# PowerManagement_Base_v2.net
KiCad netlist of a schematic drawn in Altium Designer
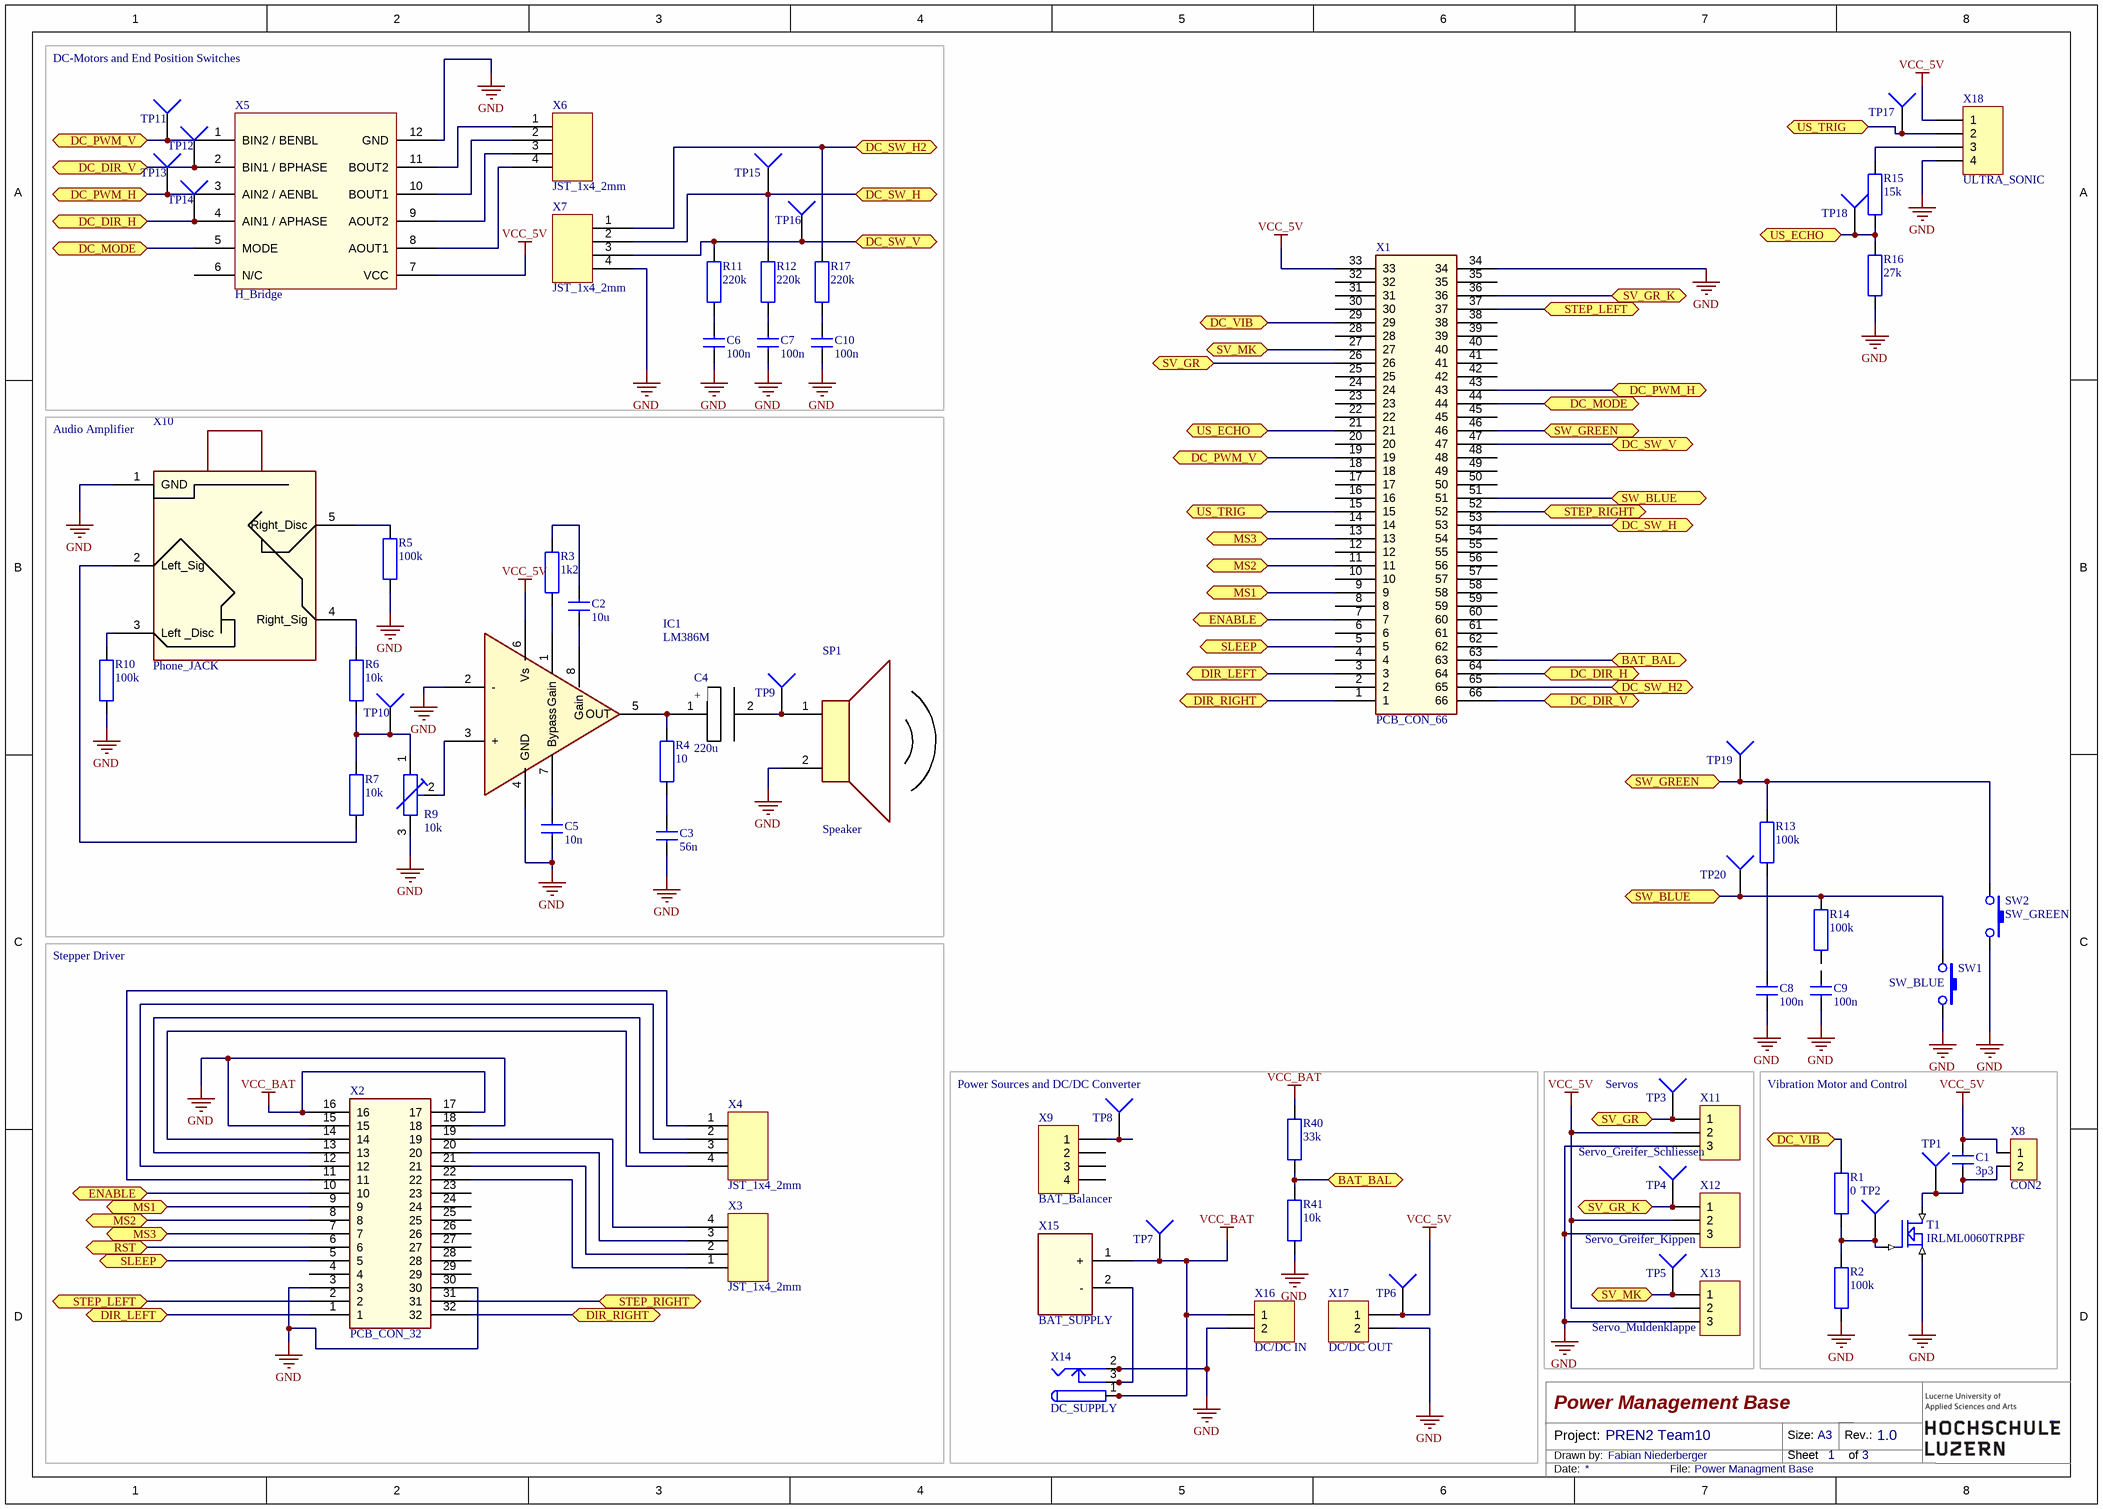
[diagram p0: PowerManagement_Base_v2.SchDoc]

(export (version "E")
  (design (tool "Eeschema 10.0.6"))
  (components
    (comp (ref "C1")
      (value "3p3")
      (footprint "0805")
      (description "Normaler Kondensator")
      (libsource (lib "DEVICE_HSLU") (part "C?"))
    )
    (comp (ref "C2")
      (value "10u")
      (footprint "0805")
      (description "Normaler Kondensator")
      (libsource (lib "DEVICE_HSLU") (part "C?"))
    )
    (comp (ref "C3")
      (value "56n")
      (footprint "0805")
      (description "Normaler Kondensator")
      (libsource (lib "DEVICE_HSLU") (part "C?"))
    )
    (comp (ref "C4")
      (value "220u")
      (footprint "Elko")
      (description "Electrolyt Capacitor")
      (libsource (lib "PREN2Lib") (part "Elko"))
    )
    (comp (ref "C5")
      (value "10n")
      (footprint "0805")
      (description "Normaler Kondensator")
      (libsource (lib "DEVICE_HSLU") (part "C?"))
    )
    (comp (ref "C6")
      (value "100n")
      (footprint "0805")
      (description "Normaler Kondensator")
      (libsource (lib "DEVICE_HSLU") (part "C?"))
    )
    (comp (ref "C7")
      (value "100n")
      (footprint "0805")
      (description "Normaler Kondensator")
      (libsource (lib "DEVICE_HSLU") (part "C?"))
    )
    (comp (ref "C8")
      (value "100n")
      (footprint "0805")
      (description "Normaler Kondensator")
      (libsource (lib "DEVICE_HSLU") (part "C?"))
    )
    (comp (ref "C9")
      (value "100n")
      (footprint "0805")
      (description "Normaler Kondensator")
      (libsource (lib "DEVICE_HSLU") (part "C?"))
    )
    (comp (ref "C10")
      (value "100n")
      (footprint "0805")
      (description "Normaler Kondensator")
      (libsource (lib "DEVICE_HSLU") (part "C?"))
    )
    (comp (ref "IC1")
      (value "LM386M")
      (footprint "SO-8")
      (description "Audio AMP in SO-8 Package")
      (libsource (lib "PREN2Lib") (part "Audio Amp"))
    )
    (comp (ref "R1")
      (value "0")
      (footprint "0805")
      (description "Normaler Widerstand")
      (libsource (lib "DEVICE_HSLU") (part "R?"))
    )
    (comp (ref "R2")
      (value "100k")
      (footprint "0805")
      (description "Normaler Widerstand")
      (libsource (lib "DEVICE_HSLU") (part "R?"))
    )
    (comp (ref "R3")
      (value "1k2")
      (footprint "0805")
      (description "Normaler Widerstand")
      (libsource (lib "DEVICE_HSLU") (part "R?"))
    )
    (comp (ref "R4")
      (value "10")
      (footprint "0805")
      (description "Normaler Widerstand")
      (libsource (lib "DEVICE_HSLU") (part "R?"))
    )
    (comp (ref "R5")
      (value "100k")
      (footprint "0805")
      (description "Normaler Widerstand")
      (libsource (lib "DEVICE_HSLU") (part "R?"))
    )
    (comp (ref "R6")
      (value "10k")
      (footprint "0805")
      (description "Normaler Widerstand")
      (libsource (lib "DEVICE_HSLU") (part "R?"))
    )
    (comp (ref "R7")
      (value "10k")
      (footprint "0805")
      (description "Normaler Widerstand")
      (libsource (lib "DEVICE_HSLU") (part "R?"))
    )
    (comp (ref "R9") (value "10k") (footprint "POT2") (libsource (lib "DEVICE_HSLU") (part "R_POT1")))
    (comp (ref "R10")
      (value "100k")
      (footprint "0805")
      (description "Normaler Widerstand")
      (libsource (lib "DEVICE_HSLU") (part "R?"))
    )
    (comp (ref "R11")
      (value "220k")
      (footprint "0805")
      (description "Normaler Widerstand")
      (libsource (lib "DEVICE_HSLU") (part "R?"))
    )
    (comp (ref "R12")
      (value "220k")
      (footprint "0805")
      (description "Normaler Widerstand")
      (libsource (lib "DEVICE_HSLU") (part "R?"))
    )
    (comp (ref "R13")
      (value "100k")
      (footprint "0805")
      (description "Normaler Widerstand")
      (libsource (lib "DEVICE_HSLU") (part "R?"))
    )
    (comp (ref "R14")
      (value "100k")
      (footprint "0805")
      (description "Normaler Widerstand")
      (libsource (lib "DEVICE_HSLU") (part "R?"))
    )
    (comp (ref "R15")
      (value "15k")
      (footprint "0805")
      (description "Normaler Widerstand")
      (libsource (lib "DEVICE_HSLU") (part "R?"))
    )
    (comp (ref "R16")
      (value "27k")
      (footprint "0805")
      (description "Normaler Widerstand")
      (libsource (lib "DEVICE_HSLU") (part "R?"))
    )
    (comp (ref "R17")
      (value "220k")
      (footprint "0805")
      (description "Normaler Widerstand")
      (libsource (lib "DEVICE_HSLU") (part "R?"))
    )
    (comp (ref "R40")
      (value "33k")
      (footprint "0805")
      (description "Normaler Widerstand")
      (libsource (lib "DEVICE_HSLU") (part "R?"))
    )
    (comp (ref "R41")
      (value "10k")
      (footprint "0805")
      (description "Normaler Widerstand")
      (libsource (lib "DEVICE_HSLU") (part "R?"))
    )
    (comp (ref "SP1")
      (value "Speaker")
      (footprint "Speaker")
      (description "8 Ohm Speaker")
      (libsource (lib "PREN2Lib") (part "Speaker"))
    )
    (comp (ref "SW1") (value "SW_BLUE") (footprint "TASTER") (libsource (lib "DEVICE_HSLU") (part "SW-PB")))
    (comp (ref "SW2") (value "SW_GREEN") (footprint "TASTER") (libsource (lib "DEVICE_HSLU") (part "SW-PB")))
    (comp (ref "T1")
      (value "IRLML0060TRPBF")
      (footprint "SOT-23")
      (libsource (lib "DEVICE_HSLU") (part "MOSFET N"))
    )
    (comp (ref "TP1")
      (value "~")
      (footprint "PIN1")
      (fields (field (name "PUBLISHER") "Altium Limited"))
      (libsource (lib "Miscellaneous Connectors") (part "Socket"))
    )
    (comp (ref "TP2")
      (value "~")
      (footprint "PIN1")
      (fields (field (name "PUBLISHER") "Altium Limited"))
      (libsource (lib "Miscellaneous Connectors") (part "Socket"))
    )
    (comp (ref "TP3")
      (value "~")
      (footprint "PIN1")
      (fields (field (name "PUBLISHER") "Altium Limited"))
      (libsource (lib "Miscellaneous Connectors") (part "Socket"))
    )
    (comp (ref "TP4")
      (value "~")
      (footprint "PIN1")
      (fields (field (name "PUBLISHER") "Altium Limited"))
      (libsource (lib "Miscellaneous Connectors") (part "Socket"))
    )
    (comp (ref "TP5")
      (value "~")
      (footprint "PIN1")
      (fields (field (name "PUBLISHER") "Altium Limited"))
      (libsource (lib "Miscellaneous Connectors") (part "Socket"))
    )
    (comp (ref "TP6")
      (value "~")
      (footprint "PIN1")
      (fields (field (name "PUBLISHER") "Altium Limited"))
      (libsource (lib "Miscellaneous Connectors") (part "Socket"))
    )
    (comp (ref "TP7")
      (value "~")
      (footprint "PIN1")
      (fields (field (name "PUBLISHER") "Altium Limited"))
      (libsource (lib "Miscellaneous Connectors") (part "Socket"))
    )
    (comp (ref "TP8")
      (value "~")
      (footprint "PIN1")
      (fields (field (name "PUBLISHER") "Altium Limited"))
      (libsource (lib "Miscellaneous Connectors") (part "Socket"))
    )
    (comp (ref "TP9")
      (value "~")
      (footprint "PIN1")
      (fields (field (name "PUBLISHER") "Altium Limited"))
      (libsource (lib "Miscellaneous Connectors") (part "Socket"))
    )
    (comp (ref "TP10")
      (value "~")
      (footprint "PIN1")
      (fields (field (name "PUBLISHER") "Altium Limited"))
      (libsource (lib "Miscellaneous Connectors") (part "Socket"))
    )
    (comp (ref "TP11")
      (value "~")
      (footprint "PIN1")
      (fields (field (name "PUBLISHER") "Altium Limited"))
      (libsource (lib "Miscellaneous Connectors") (part "Socket"))
    )
    (comp (ref "TP12")
      (value "~")
      (footprint "PIN1")
      (fields (field (name "PUBLISHER") "Altium Limited"))
      (libsource (lib "Miscellaneous Connectors") (part "Socket"))
    )
    (comp (ref "TP13")
      (value "~")
      (footprint "PIN1")
      (fields (field (name "PUBLISHER") "Altium Limited"))
      (libsource (lib "Miscellaneous Connectors") (part "Socket"))
    )
    (comp (ref "TP14")
      (value "~")
      (footprint "PIN1")
      (fields (field (name "PUBLISHER") "Altium Limited"))
      (libsource (lib "Miscellaneous Connectors") (part "Socket"))
    )
    (comp (ref "TP15")
      (value "~")
      (footprint "PIN1")
      (fields (field (name "PUBLISHER") "Altium Limited"))
      (libsource (lib "Miscellaneous Connectors") (part "Socket"))
    )
    (comp (ref "TP16")
      (value "~")
      (footprint "PIN1")
      (fields (field (name "PUBLISHER") "Altium Limited"))
      (libsource (lib "Miscellaneous Connectors") (part "Socket"))
    )
    (comp (ref "TP17")
      (value "~")
      (footprint "PIN1")
      (fields (field (name "PUBLISHER") "Altium Limited"))
      (libsource (lib "Miscellaneous Connectors") (part "Socket"))
    )
    (comp (ref "TP18")
      (value "~")
      (footprint "PIN1")
      (fields (field (name "PUBLISHER") "Altium Limited"))
      (libsource (lib "Miscellaneous Connectors") (part "Socket"))
    )
    (comp (ref "TP19")
      (value "~")
      (footprint "PIN1")
      (fields (field (name "PUBLISHER") "Altium Limited"))
      (libsource (lib "Miscellaneous Connectors") (part "Socket"))
    )
    (comp (ref "TP20")
      (value "~")
      (footprint "PIN1")
      (fields (field (name "PUBLISHER") "Altium Limited"))
      (libsource (lib "Miscellaneous Connectors") (part "Socket"))
    )
    (comp (ref "X1")
      (value "PCB_CON_66")
      (footprint "PCB_CON_66_JACK")
      (description "Connects a PCB with another. This scheme is either jack or plug, depends on footprint")
      (libsource (lib "PREN2Lib") (part "PCB_CON_66"))
    )
    (comp (ref "X2")
      (value "PCB_CON_32")
      (footprint "PCB_CON_32_JACK")
      (description "Connects a PCB with another. This scheme is either jack or plug, depends on footprint")
      (libsource (lib "PREN2Lib") (part "PCB_CON_32"))
    )
    (comp (ref "X3")
      (value "JST_1x4_2mm")
      (footprint "JST_1x4_2mm_horizontal")
      (description "JST connector single row 4 pin, 2mm grid")
      (libsource (lib "") (part "JST_1x4_2mm_2"))
    )
    (comp (ref "X4")
      (value "JST_1x4_2mm")
      (footprint "JST_1x4_2mm_horizontal")
      (description "JST connector single row 4 pin, 2mm grid")
      (libsource (lib "") (part "JST_1x4_2mm_1"))
    )
    (comp (ref "X5")
      (value "H_Bridge")
      (footprint "H_Bridge")
      (description "H-Bridge Shield")
      (libsource (lib "PREN2Lib") (part "H_Bridge"))
    )
    (comp (ref "X6")
      (value "JST_1x4_2mm")
      (footprint "JST_1x4_2mm_horizontal")
      (description "JST connector single row 4 pin, 2mm grid")
      (libsource (lib "") (part "JST_1x4_2mm_1"))
    )
    (comp (ref "X7")
      (value "JST_1x4_2mm")
      (footprint "JST_1x4_2mm_horizontal")
      (description "JST connector single row 4 pin, 2mm grid")
      (libsource (lib "PREN2Lib") (part "JST_1x4_2mm"))
    )
    (comp (ref "X8") (value "CON2") (footprint "HDR1X2") (libsource (lib "DEVICE_HSLU") (part "CON2")))
    (comp (ref "X9")
      (value "BAT_Balancer")
      (footprint "HDR1X4")
      (description "Header, 4-Pin")
      (fields (field (name "PUBLISHER") "Altium Limited"))
      (libsource (lib "") (part "Header 4_1"))
    )
    (comp (ref "X10")
      (value "Phone_JACK")
      (footprint "Audio_CON 3.5mm")
      (description "3.5 mm Phone Jack Stereo with Disconnect information")
      (libsource (lib "PREN2Lib") (part "Phone_JACK"))
    )
    (comp (ref "X11")
      (value "Servo_Greifer_Schliessen")
      (footprint "HDR1X3")
      (description "Header, 3-Pin")
      (fields (field (name "PUBLISHER") "Altium Limited"))
      (libsource (lib "Miscellaneous Connectors") (part "Header 3"))
    )
    (comp (ref "X12")
      (value "Servo_Greifer_Kippen")
      (footprint "HDR1X3")
      (description "Header, 3-Pin")
      (fields (field (name "PUBLISHER") "Altium Limited"))
      (libsource (lib "Miscellaneous Connectors") (part "Header 3"))
    )
    (comp (ref "X13")
      (value "Servo_Muldenklappe")
      (footprint "HDR1X3")
      (description "Header, 3-Pin")
      (fields (field (name "PUBLISHER") "Altium Limited"))
      (libsource (lib "Miscellaneous Connectors") (part "Header 3"))
    )
    (comp (ref "X14")
      (value "DC_SUPPLY")
      (footprint "KLD-0202")
      (description "Low Voltage Power Supply Connector")
      (fields (field (name "PUBLISHER") "Altium Limited"))
      (libsource (lib "Miscellaneous Connectors") (part "PWR2.5"))
    )
    (comp (ref "X15")
      (value "BAT_SUPPLY")
      (footprint "XT60_CON")
      (description "XT60 LiPo Accumulator Connector")
      (libsource (lib "PREN2Lib") (part "XT60_CON"))
    )
    (comp (ref "X16")
      (value "DC/DC IN")
      (footprint "HDR1X2H")
      (description "Header, 2-Pin, Right Angle")
      (fields (field (name "PUBLISHER") "Altium Limited"))
      (libsource (lib "Miscellaneous Connectors") (part "Header 2H"))
    )
    (comp (ref "X17")
      (value "DC/DC OUT")
      (footprint "HDR1X2H")
      (description "Header, 2-Pin, Right Angle")
      (fields (field (name "PUBLISHER") "Altium Limited"))
      (libsource (lib "") (part "Header 2H_1"))
    )
    (comp (ref "X18")
      (value "ULTRA_SONIC")
      (footprint "HDR1X4")
      (description "Header, 4-Pin")
      (fields (field (name "PUBLISHER") "Altium Limited"))
      (libsource (lib "Miscellaneous Connectors") (part "Header 4"))
    )
  )
  (nets
    (net (code "1") (name "/BAT_BAL") (class "Default")
      (node (ref "R40") (pin "1") (pintype "passive"))
      (node (ref "R41") (pin "2") (pintype "passive"))
      (node (ref "X1") (pin "63") (pinfunction "63_63") (pintype "passive"))
    )
    (net (code "2") (name "/DC_DIR_H") (class "Default")
      (node (ref "TP14") (pin "1") (pinfunction "1_1") (pintype "passive"))
      (node (ref "X1") (pin "64") (pinfunction "64_64") (pintype "passive"))
      (node (ref "X5") (pin "4") (pinfunction "AIN1_/_APHASE_4") (pintype "passive"))
    )
    (net (code "3") (name "/DC_DIR_V") (class "Default")
      (node (ref "TP12") (pin "1") (pinfunction "1_1") (pintype "passive"))
      (node (ref "X1") (pin "66") (pinfunction "66_66") (pintype "passive"))
      (node (ref "X5") (pin "2") (pinfunction "BIN1_/_BPHASE_2") (pintype "passive"))
    )
    (net (code "4") (name "/DC_MODE") (class "Default")
      (node (ref "X1") (pin "44") (pinfunction "44_44") (pintype "passive"))
      (node (ref "X5") (pin "5") (pinfunction "MODE_5") (pintype "passive"))
    )
    (net (code "5") (name "/DC_PWM_H") (class "Default")
      (node (ref "TP13") (pin "1") (pinfunction "1_1") (pintype "passive"))
      (node (ref "X1") (pin "43") (pinfunction "43_43") (pintype "passive"))
      (node (ref "X5") (pin "3") (pinfunction "AIN2_/_AENBL_3") (pintype "passive"))
    )
    (net (code "6") (name "/DC_PWM_V") (class "Default")
      (node (ref "TP11") (pin "1") (pinfunction "1_1") (pintype "passive"))
      (node (ref "X1") (pin "19") (pinfunction "19_19") (pintype "passive"))
      (node (ref "X5") (pin "1") (pinfunction "BIN2_/_BENBL_1") (pintype "passive"))
    )
    (net (code "7") (name "/DC_SW_H") (class "Default")
      (node (ref "R12") (pin "2") (pintype "passive"))
      (node (ref "TP15") (pin "1") (pinfunction "1_1") (pintype "passive"))
      (node (ref "X1") (pin "53") (pinfunction "53_53") (pintype "passive"))
      (node (ref "X7") (pin "2") (pintype "passive"))
    )
    (net (code "8") (name "/DC_SW_H2") (class "Default")
      (node (ref "R17") (pin "2") (pintype "passive"))
      (node (ref "X1") (pin "65") (pinfunction "65_65") (pintype "passive"))
      (node (ref "X7") (pin "1") (pintype "passive"))
    )
    (net (code "9") (name "/DC_SW_V") (class "Default")
      (node (ref "R11") (pin "2") (pintype "passive"))
      (node (ref "TP16") (pin "1") (pinfunction "1_1") (pintype "passive"))
      (node (ref "X1") (pin "47") (pinfunction "47_47") (pintype "passive"))
      (node (ref "X7") (pin "3") (pintype "passive"))
    )
    (net (code "10") (name "/DC_VIB") (class "Default")
      (node (ref "R1") (pin "2") (pintype "passive"))
      (node (ref "X1") (pin "29") (pinfunction "29_29") (pintype "passive"))
    )
    (net (code "11") (name "/DIR_LEFT") (class "Default")
      (node (ref "X1") (pin "3") (pinfunction "3_3") (pintype "passive"))
      (node (ref "X2") (pin "1") (pinfunction "1_1") (pintype "passive"))
    )
    (net (code "12") (name "/DIR_RIGHT") (class "Default")
      (node (ref "X1") (pin "1") (pinfunction "1_1") (pintype "passive"))
      (node (ref "X2") (pin "32") (pinfunction "32_32") (pintype "passive"))
    )
    (net (code "13") (name "/ENABLE") (class "Default")
      (node (ref "X1") (pin "7") (pinfunction "7_7") (pintype "passive"))
      (node (ref "X2") (pin "10") (pinfunction "10_10") (pintype "passive"))
    )
    (net (code "14") (name "/MS1") (class "Default")
      (node (ref "X1") (pin "9") (pinfunction "9_9") (pintype "passive"))
      (node (ref "X2") (pin "9") (pinfunction "9_9") (pintype "passive"))
    )
    (net (code "15") (name "/MS2") (class "Default")
      (node (ref "X1") (pin "11") (pinfunction "11_11") (pintype "passive"))
      (node (ref "X2") (pin "8") (pinfunction "8_8") (pintype "passive"))
    )
    (net (code "16") (name "/MS3") (class "Default")
      (node (ref "X1") (pin "13") (pinfunction "13_13") (pintype "passive"))
      (node (ref "X2") (pin "7") (pinfunction "7_7") (pintype "passive"))
    )
    (net (code "17") (name "/RST") (class "Default")
      (node (ref "X2") (pin "6") (pinfunction "6_6") (pintype "passive"))
    )
    (net (code "18") (name "/SLEEP") (class "Default")
      (node (ref "X1") (pin "5") (pinfunction "5_5") (pintype "passive"))
      (node (ref "X2") (pin "5") (pinfunction "5_5") (pintype "passive"))
    )
    (net (code "19") (name "/STEP_LEFT") (class "Default")
      (node (ref "X1") (pin "37") (pinfunction "37_37") (pintype "passive"))
      (node (ref "X2") (pin "2") (pinfunction "2_2") (pintype "passive"))
    )
    (net (code "20") (name "/STEP_RIGHT") (class "Default")
      (node (ref "X1") (pin "52") (pinfunction "52_52") (pintype "passive"))
      (node (ref "X2") (pin "31") (pinfunction "31_31") (pintype "passive"))
    )
    (net (code "21") (name "/SV_GR") (class "Default")
      (node (ref "TP3") (pin "1") (pinfunction "1_1") (pintype "passive"))
      (node (ref "X1") (pin "26") (pinfunction "26_26") (pintype "passive"))
      (node (ref "X11") (pin "1") (pinfunction "1_1") (pintype "passive"))
    )
    (net (code "22") (name "/SV_GR_K") (class "Default")
      (node (ref "TP4") (pin "1") (pinfunction "1_1") (pintype "passive"))
      (node (ref "X1") (pin "36") (pinfunction "36_36") (pintype "passive"))
      (node (ref "X12") (pin "1") (pinfunction "1_1") (pintype "passive"))
    )
    (net (code "23") (name "/SV_MK") (class "Default")
      (node (ref "TP5") (pin "1") (pinfunction "1_1") (pintype "passive"))
      (node (ref "X1") (pin "27") (pinfunction "27_27") (pintype "passive"))
      (node (ref "X13") (pin "1") (pinfunction "1_1") (pintype "passive"))
    )
    (net (code "24") (name "/SW_BLUE") (class "Default")
      (node (ref "R14") (pin "2") (pintype "passive"))
      (node (ref "SW1") (pin "1") (pintype "passive"))
      (node (ref "TP20") (pin "1") (pinfunction "1_1") (pintype "passive"))
      (node (ref "X1") (pin "51") (pinfunction "51_51") (pintype "passive"))
    )
    (net (code "25") (name "/SW_GREEN") (class "Default")
      (node (ref "R13") (pin "2") (pintype "passive"))
      (node (ref "SW2") (pin "1") (pintype "passive"))
      (node (ref "TP19") (pin "1") (pinfunction "1_1") (pintype "passive"))
      (node (ref "X1") (pin "46") (pinfunction "46_46") (pintype "passive"))
    )
    (net (code "26") (name "/US_ECHO") (class "Default")
      (node (ref "R15") (pin "1") (pintype "passive"))
      (node (ref "R16") (pin "2") (pintype "passive"))
      (node (ref "TP18") (pin "1") (pinfunction "1_1") (pintype "passive"))
      (node (ref "X1") (pin "21") (pinfunction "21_21") (pintype "passive"))
    )
    (net (code "27") (name "/US_TRIG") (class "Default")
      (node (ref "TP17") (pin "1") (pinfunction "1_1") (pintype "passive"))
      (node (ref "X1") (pin "15") (pinfunction "15_15") (pintype "passive"))
      (node (ref "X18") (pin "2") (pinfunction "2_2") (pintype "passive"))
    )
    (net (code "28") (name "GND") (class "Default")
      (node (ref "C10") (pin "2") (pinfunction "2_2") (pintype "passive"))
      (node (ref "C3") (pin "2") (pinfunction "2_2") (pintype "passive"))
      (node (ref "C5") (pin "2") (pinfunction "2_2") (pintype "passive"))
      (node (ref "C6") (pin "2") (pinfunction "2_2") (pintype "passive"))
      (node (ref "C7") (pin "2") (pinfunction "2_2") (pintype "passive"))
      (node (ref "C8") (pin "2") (pinfunction "2_2") (pintype "passive"))
      (node (ref "C9") (pin "2") (pinfunction "2_2") (pintype "passive"))
      (node (ref "IC1") (pin "2") (pinfunction "-_2") (pintype "passive"))
      (node (ref "IC1") (pin "4") (pinfunction "GND_4") (pintype "passive"))
      (node (ref "R10") (pin "1") (pintype "passive"))
      (node (ref "R16") (pin "1") (pintype "passive"))
      (node (ref "R2") (pin "1") (pintype "passive"))
      (node (ref "R41") (pin "1") (pintype "passive"))
      (node (ref "R5") (pin "1") (pintype "passive"))
      (node (ref "R9") (pin "3") (pintype "passive"))
      (node (ref "SP1") (pin "2") (pinfunction "2_2") (pintype "passive"))
      (node (ref "SW1") (pin "2") (pintype "passive"))
      (node (ref "SW2") (pin "2") (pintype "passive"))
      (node (ref "T1") (pin "SOURCE") (pinfunction "SOURCE_SOURCE") (pintype "input"))
      (node (ref "X1") (pin "34") (pinfunction "34_34") (pintype "passive"))
      (node (ref "X10") (pin "1") (pinfunction "GND_1") (pintype "passive"))
      (node (ref "X11") (pin "3") (pinfunction "3_3") (pintype "passive"))
      (node (ref "X12") (pin "3") (pinfunction "3_3") (pintype "passive"))
      (node (ref "X13") (pin "3") (pinfunction "3_3") (pintype "passive"))
      (node (ref "X14") (pin "2") (pinfunction "2_2") (pintype "power_in"))
      (node (ref "X14") (pin "2A") (pinfunction "2A_2A") (pintype "power_in"))
      (node (ref "X14") (pin "2B") (pinfunction "2B_2B") (pintype "power_in"))
      (node (ref "X16") (pin "2") (pinfunction "2_2") (pintype "passive"))
      (node (ref "X17") (pin "2") (pinfunction "2_2") (pintype "passive"))
      (node (ref "X18") (pin "4") (pinfunction "4_4") (pintype "passive"))
      (node (ref "X2") (pin "15") (pinfunction "15_15") (pintype "passive"))
      (node (ref "X2") (pin "18") (pinfunction "18_18") (pintype "passive"))
      (node (ref "X2") (pin "3") (pinfunction "3_3") (pintype "passive"))
      (node (ref "X2") (pin "30") (pinfunction "30_30") (pintype "passive"))
      (node (ref "X5") (pin "12") (pinfunction "GND_12") (pintype "power_in"))
      (node (ref "X7") (pin "4") (pintype "passive"))
    )
    (net (code "29") (name "Net-(C1-Pad1)") (class "Default")
      (node (ref "C1") (pin "1") (pinfunction "1_1") (pintype "passive"))
      (node (ref "T1") (pin "DRAIN") (pinfunction "DRAIN_DRAIN") (pintype "input"))
      (node (ref "TP1") (pin "1") (pinfunction "1_1") (pintype "passive"))
      (node (ref "X8") (pin "2") (pinfunction "2_2") (pintype "passive"))
    )
    (net (code "30") (name "Net-(C2-Pad1)") (class "Default")
      (node (ref "C2") (pin "1") (pinfunction "1_1") (pintype "passive"))
      (node (ref "R3") (pin "2") (pintype "passive"))
    )
    (net (code "31") (name "Net-(C2-Pad2)") (class "Default")
      (node (ref "C2") (pin "2") (pinfunction "2_2") (pintype "passive"))
      (node (ref "IC1") (pin "8") (pinfunction "Gain_8") (pintype "passive"))
    )
    (net (code "32") (name "Net-(C3-Pad1)") (class "Default")
      (node (ref "C3") (pin "1") (pinfunction "1_1") (pintype "passive"))
      (node (ref "R4") (pin "1") (pintype "passive"))
    )
    (net (code "33") (name "Net-(C4-Pad2)") (class "Default")
      (node (ref "C4") (pin "2") (pintype "passive"))
      (node (ref "SP1") (pin "1") (pinfunction "1_1") (pintype "passive"))
      (node (ref "TP9") (pin "1") (pinfunction "1_1") (pintype "passive"))
    )
    (net (code "34") (name "Net-(C6-Pad1)") (class "Default")
      (node (ref "C6") (pin "1") (pinfunction "1_1") (pintype "passive"))
      (node (ref "R11") (pin "1") (pintype "passive"))
    )
    (net (code "35") (name "Net-(C7-Pad1)") (class "Default")
      (node (ref "C7") (pin "1") (pinfunction "1_1") (pintype "passive"))
      (node (ref "R12") (pin "1") (pintype "passive"))
    )
    (net (code "36") (name "Net-(C8-Pad1)") (class "Default")
      (node (ref "C8") (pin "1") (pinfunction "1_1") (pintype "passive"))
      (node (ref "R13") (pin "1") (pintype "passive"))
    )
    (net (code "37") (name "Net-(C10-Pad1)") (class "Default")
      (node (ref "C10") (pin "1") (pinfunction "1_1") (pintype "passive"))
      (node (ref "R17") (pin "1") (pintype "passive"))
    )
    (net (code "38") (name "Net-(IC1-+)") (class "Default")
      (node (ref "IC1") (pin "3") (pinfunction "+_3") (pintype "passive"))
      (node (ref "R9") (pin "2") (pintype "passive"))
    )
    (net (code "39") (name "Net-(IC1-Bypass)") (class "Default")
      (node (ref "C5") (pin "1") (pinfunction "1_1") (pintype "passive"))
      (node (ref "IC1") (pin "7") (pinfunction "Bypass_7") (pintype "passive"))
    )
    (net (code "40") (name "Net-(IC1-Gain-Pad1)") (class "Default")
      (node (ref "IC1") (pin "1") (pinfunction "Gain_1") (pintype "passive"))
      (node (ref "R3") (pin "1") (pintype "passive"))
    )
    (net (code "41") (name "Net-(IC1-OUT)") (class "Default")
      (node (ref "C4") (pin "1") (pintype "passive"))
      (node (ref "IC1") (pin "5") (pinfunction "OUT_5") (pintype "passive"))
      (node (ref "R4") (pin "2") (pintype "passive"))
    )
    (net (code "42") (name "Net-(R1-Pad1)") (class "Default")
      (node (ref "R1") (pin "1") (pintype "passive"))
      (node (ref "R2") (pin "2") (pintype "passive"))
      (node (ref "T1") (pin "GATE") (pinfunction "GATE_GATE") (pintype "input"))
      (node (ref "TP2") (pin "1") (pinfunction "1_1") (pintype "passive"))
    )
    (net (code "43") (name "Net-(R6-Pad2)") (class "Default")
      (node (ref "R6") (pin "2") (pintype "passive"))
      (node (ref "R7") (pin "1") (pintype "passive"))
      (node (ref "R9") (pin "1") (pintype "passive"))
      (node (ref "TP10") (pin "1") (pinfunction "1_1") (pintype "passive"))
    )
    (net (code "44") (name "Net-(R15-Pad2)") (class "Default")
      (node (ref "R15") (pin "2") (pintype "passive"))
      (node (ref "X18") (pin "3") (pinfunction "3_3") (pintype "passive"))
    )
    (net (code "45") (name "Net-(TP8-Pad1)") (class "Default")
      (node (ref "TP8") (pin "1") (pinfunction "1_1") (pintype "passive"))
      (node (ref "X9") (pin "1") (pinfunction "1_1") (pintype "passive"))
    )
    (net (code "46") (name "Net-(X2-Pad11)") (class "Default")
      (node (ref "X2") (pin "11") (pinfunction "11_11") (pintype "passive"))
      (node (ref "X4") (pin "1") (pintype "passive"))
    )
    (net (code "47") (name "Net-(X2-Pad12)") (class "Default")
      (node (ref "X2") (pin "12") (pinfunction "12_12") (pintype "passive"))
      (node (ref "X4") (pin "2") (pintype "passive"))
    )
    (net (code "48") (name "Net-(X2-Pad13)") (class "Default")
      (node (ref "X2") (pin "13") (pinfunction "13_13") (pintype "passive"))
      (node (ref "X4") (pin "3") (pintype "passive"))
    )
    (net (code "49") (name "Net-(X2-Pad14)") (class "Default")
      (node (ref "X2") (pin "14") (pinfunction "14_14") (pintype "passive"))
      (node (ref "X4") (pin "4") (pintype "passive"))
    )
    (net (code "50") (name "Net-(X2-Pad19)") (class "Default")
      (node (ref "X2") (pin "19") (pinfunction "19_19") (pintype "passive"))
      (node (ref "X3") (pin "4") (pintype "passive"))
    )
    (net (code "51") (name "Net-(X2-Pad20)") (class "Default")
      (node (ref "X2") (pin "20") (pinfunction "20_20") (pintype "passive"))
      (node (ref "X3") (pin "3") (pintype "passive"))
    )
    (net (code "52") (name "Net-(X2-Pad21)") (class "Default")
      (node (ref "X2") (pin "21") (pinfunction "21_21") (pintype "passive"))
      (node (ref "X3") (pin "2") (pintype "passive"))
    )
    (net (code "53") (name "Net-(X2-Pad22)") (class "Default")
      (node (ref "X2") (pin "22") (pinfunction "22_22") (pintype "passive"))
      (node (ref "X3") (pin "1") (pintype "passive"))
    )
    (net (code "54") (name "Net-(X5-AOUT1)") (class "Default")
      (node (ref "X5") (pin "8") (pinfunction "AOUT1_8") (pintype "passive"))
      (node (ref "X6") (pin "4") (pintype "passive"))
    )
    (net (code "55") (name "Net-(X5-AOUT2)") (class "Default")
      (node (ref "X5") (pin "9") (pinfunction "AOUT2_9") (pintype "passive"))
      (node (ref "X6") (pin "3") (pintype "passive"))
    )
    (net (code "56") (name "Net-(X5-BOUT1)") (class "Default")
      (node (ref "X5") (pin "10") (pinfunction "BOUT1_10") (pintype "passive"))
      (node (ref "X6") (pin "2") (pintype "passive"))
    )
    (net (code "57") (name "Net-(X5-BOUT2)") (class "Default")
      (node (ref "X5") (pin "11") (pinfunction "BOUT2_11") (pintype "passive"))
      (node (ref "X6") (pin "1") (pintype "passive"))
    )
    (net (code "58") (name "Net-(X10-Left_Sig)") (class "Default")
      (node (ref "R7") (pin "2") (pintype "passive"))
      (node (ref "X10") (pin "2") (pinfunction "Left_Sig_2") (pintype "passive"))
    )
    (net (code "59") (name "Net-(X10-Left__Disc)") (class "Default")
      (node (ref "R10") (pin "2") (pintype "passive"))
      (node (ref "X10") (pin "3") (pinfunction "Left__Disc_3") (pintype "passive"))
    )
    (net (code "60") (name "Net-(X10-Right_Disc)") (class "Default")
      (node (ref "R5") (pin "2") (pintype "passive"))
      (node (ref "X10") (pin "5") (pinfunction "Right_Disc_5") (pintype "passive"))
    )
    (net (code "61") (name "Net-(X10-Right_Sig)") (class "Default")
      (node (ref "R6") (pin "1") (pintype "passive"))
      (node (ref "X10") (pin "4") (pinfunction "Right_Sig_4") (pintype "passive"))
    )
    (net (code "62") (name "Net-(X15--)") (class "Default")
      (node (ref "X14") (pin "3") (pinfunction "3_3") (pintype "power_in"))
      (node (ref "X14") (pin "3A") (pinfunction "3A_3A") (pintype "power_in"))
      (node (ref "X14") (pin "3B") (pinfunction "3B_3B") (pintype "power_in"))
      (node (ref "X15") (pin "2") (pinfunction "-_2") (pintype "passive"))
    )
    (net (code "63") (name "VCC_5V") (class "Default")
      (node (ref "C1") (pin "2") (pinfunction "2_2") (pintype "passive"))
      (node (ref "IC1") (pin "6") (pinfunction "Vs_6") (pintype "passive"))
      (node (ref "TP6") (pin "1") (pinfunction "1_1") (pintype "passive"))
      (node (ref "X1") (pin "33") (pinfunction "33_33") (pintype "passive"))
      (node (ref "X11") (pin "2") (pinfunction "2_2") (pintype "passive"))
      (node (ref "X12") (pin "2") (pinfunction "2_2") (pintype "passive"))
      (node (ref "X13") (pin "2") (pinfunction "2_2") (pintype "passive"))
      (node (ref "X17") (pin "1") (pinfunction "1_1") (pintype "passive"))
      (node (ref "X18") (pin "1") (pinfunction "1_1") (pintype "passive"))
      (node (ref "X5") (pin "7") (pinfunction "VCC_7") (pintype "power_in"))
      (node (ref "X8") (pin "1") (pinfunction "1_1") (pintype "passive"))
    )
    (net (code "64") (name "VCC_BAT") (class "Default")
      (node (ref "R40") (pin "2") (pintype "passive"))
      (node (ref "TP7") (pin "1") (pinfunction "1_1") (pintype "passive"))
      (node (ref "X14") (pin "1") (pinfunction "1_1") (pintype "power_in"))
      (node (ref "X14") (pin "1A") (pinfunction "1A_1A") (pintype "power_in"))
      (node (ref "X14") (pin "1B") (pinfunction "1B_1B") (pintype "power_in"))
      (node (ref "X15") (pin "1") (pinfunction "+_1") (pintype "passive"))
      (node (ref "X16") (pin "1") (pinfunction "1_1") (pintype "passive"))
      (node (ref "X2") (pin "16") (pinfunction "16_16") (pintype "passive"))
      (node (ref "X2") (pin "17") (pinfunction "17_17") (pintype "passive"))
    )
    (net (code "65") (name "unconnected-(C9-Pad1)") (class "Default")
      (node (ref "C9") (pin "1") (pinfunction "1_1") (pintype "passive"))
    )
    (net (code "66") (name "unconnected-(R14-Pad1)") (class "Default")
      (node (ref "R14") (pin "1") (pintype "passive"))
    )
    (net (code "67") (name "unconnected-(X1-Pad2)") (class "Default")
      (node (ref "X1") (pin "2") (pinfunction "2_2") (pintype "passive"))
    )
    (net (code "68") (name "unconnected-(X1-Pad4)") (class "Default")
      (node (ref "X1") (pin "4") (pinfunction "4_4") (pintype "passive"))
    )
    (net (code "69") (name "unconnected-(X1-Pad6)") (class "Default")
      (node (ref "X1") (pin "6") (pinfunction "6_6") (pintype "passive"))
    )
    (net (code "70") (name "unconnected-(X1-Pad8)") (class "Default")
      (node (ref "X1") (pin "8") (pinfunction "8_8") (pintype "passive"))
    )
    (net (code "71") (name "unconnected-(X1-Pad10)") (class "Default")
      (node (ref "X1") (pin "10") (pinfunction "10_10") (pintype "passive"))
    )
    (net (code "72") (name "unconnected-(X1-Pad12)") (class "Default")
      (node (ref "X1") (pin "12") (pinfunction "12_12") (pintype "passive"))
    )
    (net (code "73") (name "unconnected-(X1-Pad14)") (class "Default")
      (node (ref "X1") (pin "14") (pinfunction "14_14") (pintype "passive"))
    )
    (net (code "74") (name "unconnected-(X1-Pad16)") (class "Default")
      (node (ref "X1") (pin "16") (pinfunction "16_16") (pintype "passive"))
    )
    (net (code "75") (name "unconnected-(X1-Pad17)") (class "Default")
      (node (ref "X1") (pin "17") (pinfunction "17_17") (pintype "passive"))
    )
    (net (code "76") (name "unconnected-(X1-Pad18)") (class "Default")
      (node (ref "X1") (pin "18") (pinfunction "18_18") (pintype "passive"))
    )
    (net (code "77") (name "unconnected-(X1-Pad20)") (class "Default")
      (node (ref "X1") (pin "20") (pinfunction "20_20") (pintype "passive"))
    )
    (net (code "78") (name "unconnected-(X1-Pad22)") (class "Default")
      (node (ref "X1") (pin "22") (pinfunction "22_22") (pintype "passive"))
    )
    (net (code "79") (name "unconnected-(X1-Pad23)") (class "Default")
      (node (ref "X1") (pin "23") (pinfunction "23_23") (pintype "passive"))
    )
    (net (code "80") (name "unconnected-(X1-Pad24)") (class "Default")
      (node (ref "X1") (pin "24") (pinfunction "24_24") (pintype "passive"))
    )
    (net (code "81") (name "unconnected-(X1-Pad25)") (class "Default")
      (node (ref "X1") (pin "25") (pinfunction "25_25") (pintype "passive"))
    )
    (net (code "82") (name "unconnected-(X1-Pad28)") (class "Default")
      (node (ref "X1") (pin "28") (pinfunction "28_28") (pintype "passive"))
    )
    (net (code "83") (name "unconnected-(X1-Pad30)") (class "Default")
      (node (ref "X1") (pin "30") (pinfunction "30_30") (pintype "passive"))
    )
    (net (code "84") (name "unconnected-(X1-Pad31)") (class "Default")
      (node (ref "X1") (pin "31") (pinfunction "31_31") (pintype "passive"))
    )
    (net (code "85") (name "unconnected-(X1-Pad32)") (class "Default")
      (node (ref "X1") (pin "32") (pinfunction "32_32") (pintype "passive"))
    )
    (net (code "86") (name "unconnected-(X1-Pad35)") (class "Default")
      (node (ref "X1") (pin "35") (pinfunction "35_35") (pintype "passive"))
    )
    (net (code "87") (name "unconnected-(X1-Pad38)") (class "Default")
      (node (ref "X1") (pin "38") (pinfunction "38_38") (pintype "passive"))
    )
    (net (code "88") (name "unconnected-(X1-Pad39)") (class "Default")
      (node (ref "X1") (pin "39") (pinfunction "39_39") (pintype "passive"))
    )
    (net (code "89") (name "unconnected-(X1-Pad40)") (class "Default")
      (node (ref "X1") (pin "40") (pinfunction "40_40") (pintype "passive"))
    )
    (net (code "90") (name "unconnected-(X1-Pad41)") (class "Default")
      (node (ref "X1") (pin "41") (pinfunction "41_41") (pintype "passive"))
    )
    (net (code "91") (name "unconnected-(X1-Pad42)") (class "Default")
      (node (ref "X1") (pin "42") (pinfunction "42_42") (pintype "passive"))
    )
    (net (code "92") (name "unconnected-(X1-Pad45)") (class "Default")
      (node (ref "X1") (pin "45") (pinfunction "45_45") (pintype "passive"))
    )
    (net (code "93") (name "unconnected-(X1-Pad48)") (class "Default")
      (node (ref "X1") (pin "48") (pinfunction "48_48") (pintype "passive"))
    )
    (net (code "94") (name "unconnected-(X1-Pad49)") (class "Default")
      (node (ref "X1") (pin "49") (pinfunction "49_49") (pintype "passive"))
    )
    (net (code "95") (name "unconnected-(X1-Pad50)") (class "Default")
      (node (ref "X1") (pin "50") (pinfunction "50_50") (pintype "passive"))
    )
    (net (code "96") (name "unconnected-(X1-Pad54)") (class "Default")
      (node (ref "X1") (pin "54") (pinfunction "54_54") (pintype "passive"))
    )
    (net (code "97") (name "unconnected-(X1-Pad55)") (class "Default")
      (node (ref "X1") (pin "55") (pinfunction "55_55") (pintype "passive"))
    )
    (net (code "98") (name "unconnected-(X1-Pad56)") (class "Default")
      (node (ref "X1") (pin "56") (pinfunction "56_56") (pintype "passive"))
    )
    (net (code "99") (name "unconnected-(X1-Pad57)") (class "Default")
      (node (ref "X1") (pin "57") (pinfunction "57_57") (pintype "passive"))
    )
    (net (code "100") (name "unconnected-(X1-Pad58)") (class "Default")
      (node (ref "X1") (pin "58") (pinfunction "58_58") (pintype "passive"))
    )
    (net (code "101") (name "unconnected-(X1-Pad59)") (class "Default")
      (node (ref "X1") (pin "59") (pinfunction "59_59") (pintype "passive"))
    )
    (net (code "102") (name "unconnected-(X1-Pad60)") (class "Default")
      (node (ref "X1") (pin "60") (pinfunction "60_60") (pintype "passive"))
    )
    (net (code "103") (name "unconnected-(X1-Pad61)") (class "Default")
      (node (ref "X1") (pin "61") (pinfunction "61_61") (pintype "passive"))
    )
    (net (code "104") (name "unconnected-(X1-Pad62)") (class "Default")
      (node (ref "X1") (pin "62") (pinfunction "62_62") (pintype "passive"))
    )
    (net (code "105") (name "unconnected-(X2-Pad4)") (class "Default")
      (node (ref "X2") (pin "4") (pinfunction "4_4") (pintype "passive"))
    )
    (net (code "106") (name "unconnected-(X2-Pad23)") (class "Default")
      (node (ref "X2") (pin "23") (pinfunction "23_23") (pintype "passive"))
    )
    (net (code "107") (name "unconnected-(X2-Pad24)") (class "Default")
      (node (ref "X2") (pin "24") (pinfunction "24_24") (pintype "passive"))
    )
    (net (code "108") (name "unconnected-(X2-Pad25)") (class "Default")
      (node (ref "X2") (pin "25") (pinfunction "25_25") (pintype "passive"))
    )
    (net (code "109") (name "unconnected-(X2-Pad26)") (class "Default")
      (node (ref "X2") (pin "26") (pinfunction "26_26") (pintype "passive"))
    )
    (net (code "110") (name "unconnected-(X2-Pad27)") (class "Default")
      (node (ref "X2") (pin "27") (pinfunction "27_27") (pintype "passive"))
    )
    (net (code "111") (name "unconnected-(X2-Pad28)") (class "Default")
      (node (ref "X2") (pin "28") (pinfunction "28_28") (pintype "passive"))
    )
    (net (code "112") (name "unconnected-(X2-Pad29)") (class "Default")
      (node (ref "X2") (pin "29") (pinfunction "29_29") (pintype "passive"))
    )
    (net (code "113") (name "unconnected-(X5-N{slash}C-Pad6)") (class "Default")
      (node (ref "X5") (pin "6") (pinfunction "N/C_6") (pintype "passive"))
    )
    (net (code "114") (name "unconnected-(X9-Pad2)") (class "Default")
      (node (ref "X9") (pin "2") (pinfunction "2_2") (pintype "passive"))
    )
    (net (code "115") (name "unconnected-(X9-Pad3)") (class "Default")
      (node (ref "X9") (pin "3") (pinfunction "3_3") (pintype "passive"))
    )
    (net (code "116") (name "unconnected-(X9-Pad4)") (class "Default")
      (node (ref "X9") (pin "4") (pinfunction "4_4") (pintype "passive"))
    )
  )
)
